# Sheet1.net
KiCad netlist of a schematic drawn in Altium Designer
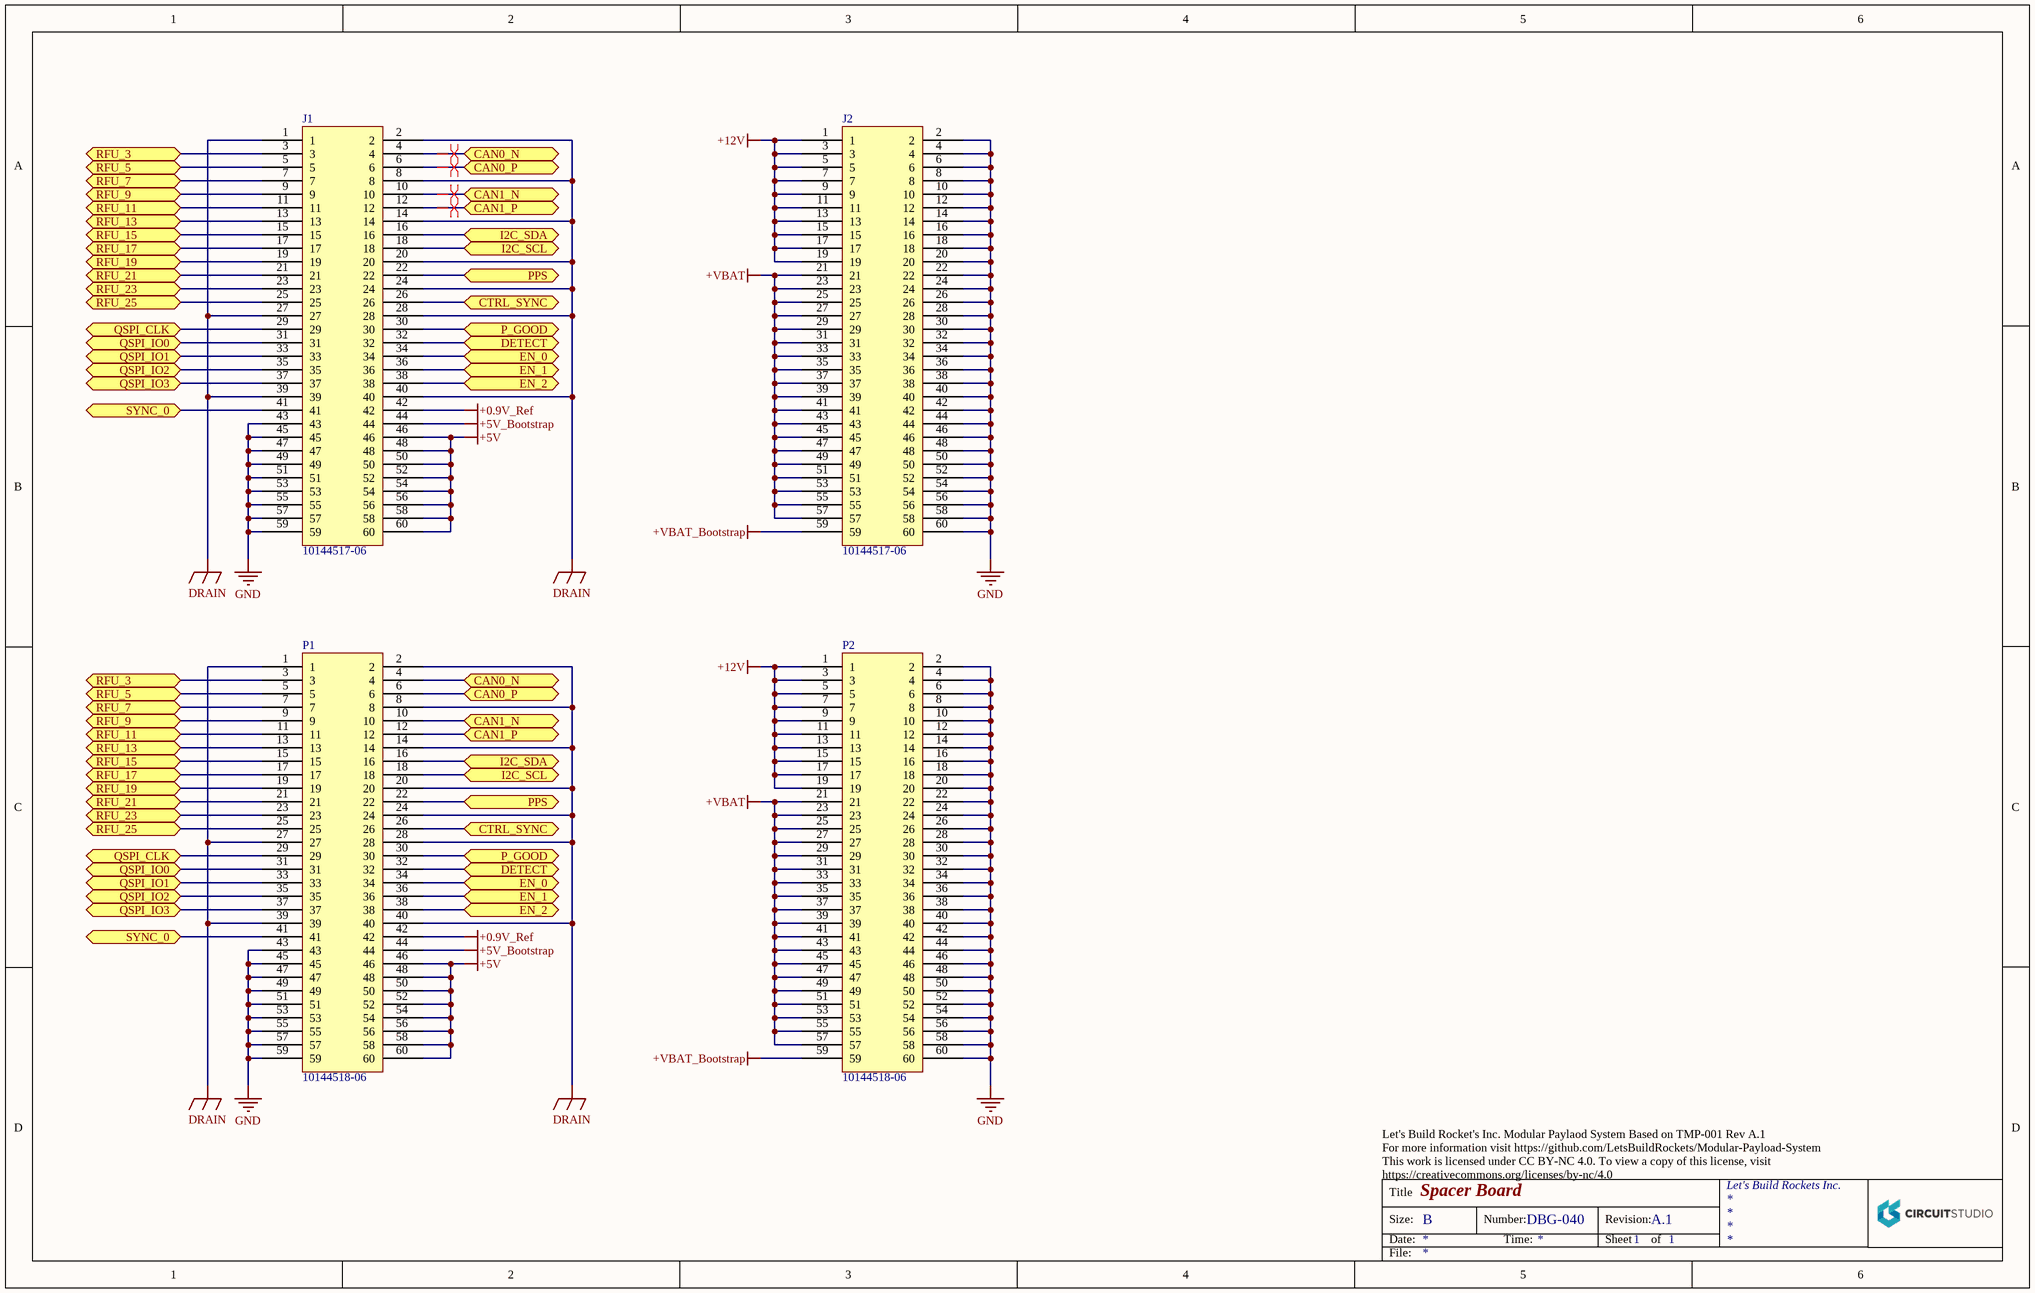
[diagram p0: Sheet1.SchDoc]

(export (version "E")
  (design (tool "Eeschema 10.0.6"))
  (components
    (comp (ref "J1")
      (value "10144517-06")
      (footprint "10144517-062802LF")
      (libsource (lib "ModularPayload") (part "10144517-06"))
    )
    (comp (ref "J2")
      (value "10144517-06")
      (footprint "10144517-062802LF")
      (libsource (lib "ModularPayload") (part "10144517-06"))
    )
    (comp (ref "P1")
      (value "10144518-06")
      (footprint "10144518-064802LF")
      (libsource (lib "ModularPayload") (part "10144518-06"))
    )
    (comp (ref "P2")
      (value "10144518-06")
      (footprint "10144518-064802LF")
      (libsource (lib "ModularPayload") (part "10144518-06"))
    )
  )
  (nets
    (net (code "1") (name "+0.9V_Ref") (class "Default")
      (node (ref "J1") (pin "42") (pinfunction "42_42") (pintype "passive"))
      (node (ref "P1") (pin "42") (pinfunction "42_42") (pintype "passive"))
    )
    (net (code "2") (name "+5V") (class "Default")
      (node (ref "J1") (pin "46") (pinfunction "46_46") (pintype "passive"))
      (node (ref "J1") (pin "48") (pinfunction "48_48") (pintype "passive"))
      (node (ref "J1") (pin "50") (pinfunction "50_50") (pintype "passive"))
      (node (ref "J1") (pin "52") (pinfunction "52_52") (pintype "passive"))
      (node (ref "J1") (pin "54") (pinfunction "54_54") (pintype "passive"))
      (node (ref "J1") (pin "56") (pinfunction "56_56") (pintype "passive"))
      (node (ref "J1") (pin "58") (pinfunction "58_58") (pintype "passive"))
      (node (ref "J1") (pin "60") (pinfunction "60_60") (pintype "passive"))
      (node (ref "P1") (pin "46") (pinfunction "46_46") (pintype "passive"))
      (node (ref "P1") (pin "48") (pinfunction "48_48") (pintype "passive"))
      (node (ref "P1") (pin "50") (pinfunction "50_50") (pintype "passive"))
      (node (ref "P1") (pin "52") (pinfunction "52_52") (pintype "passive"))
      (node (ref "P1") (pin "54") (pinfunction "54_54") (pintype "passive"))
      (node (ref "P1") (pin "56") (pinfunction "56_56") (pintype "passive"))
      (node (ref "P1") (pin "58") (pinfunction "58_58") (pintype "passive"))
      (node (ref "P1") (pin "60") (pinfunction "60_60") (pintype "passive"))
    )
    (net (code "3") (name "+5V_Bootstrap") (class "Default")
      (node (ref "J1") (pin "44") (pinfunction "44_44") (pintype "passive"))
      (node (ref "P1") (pin "44") (pinfunction "44_44") (pintype "passive"))
    )
    (net (code "4") (name "+12V") (class "Default")
      (node (ref "J2") (pin "1") (pinfunction "1_1") (pintype "passive"))
      (node (ref "J2") (pin "11") (pinfunction "11_11") (pintype "passive"))
      (node (ref "J2") (pin "13") (pinfunction "13_13") (pintype "passive"))
      (node (ref "J2") (pin "15") (pinfunction "15_15") (pintype "passive"))
      (node (ref "J2") (pin "17") (pinfunction "17_17") (pintype "passive"))
      (node (ref "J2") (pin "19") (pinfunction "19_19") (pintype "passive"))
      (node (ref "J2") (pin "3") (pinfunction "3_3") (pintype "passive"))
      (node (ref "J2") (pin "5") (pinfunction "5_5") (pintype "passive"))
      (node (ref "J2") (pin "7") (pinfunction "7_7") (pintype "passive"))
      (node (ref "J2") (pin "9") (pinfunction "9_9") (pintype "passive"))
      (node (ref "P2") (pin "1") (pinfunction "1_1") (pintype "passive"))
      (node (ref "P2") (pin "11") (pinfunction "11_11") (pintype "passive"))
      (node (ref "P2") (pin "13") (pinfunction "13_13") (pintype "passive"))
      (node (ref "P2") (pin "15") (pinfunction "15_15") (pintype "passive"))
      (node (ref "P2") (pin "17") (pinfunction "17_17") (pintype "passive"))
      (node (ref "P2") (pin "19") (pinfunction "19_19") (pintype "passive"))
      (node (ref "P2") (pin "3") (pinfunction "3_3") (pintype "passive"))
      (node (ref "P2") (pin "5") (pinfunction "5_5") (pintype "passive"))
      (node (ref "P2") (pin "7") (pinfunction "7_7") (pintype "passive"))
      (node (ref "P2") (pin "9") (pinfunction "9_9") (pintype "passive"))
    )
    (net (code "5") (name "+VBAT") (class "Default")
      (node (ref "J2") (pin "21") (pinfunction "21_21") (pintype "passive"))
      (node (ref "J2") (pin "23") (pinfunction "23_23") (pintype "passive"))
      (node (ref "J2") (pin "25") (pinfunction "25_25") (pintype "passive"))
      (node (ref "J2") (pin "27") (pinfunction "27_27") (pintype "passive"))
      (node (ref "J2") (pin "29") (pinfunction "29_29") (pintype "passive"))
      (node (ref "J2") (pin "31") (pinfunction "31_31") (pintype "passive"))
      (node (ref "J2") (pin "33") (pinfunction "33_33") (pintype "passive"))
      (node (ref "J2") (pin "35") (pinfunction "35_35") (pintype "passive"))
      (node (ref "J2") (pin "37") (pinfunction "37_37") (pintype "passive"))
      (node (ref "J2") (pin "39") (pinfunction "39_39") (pintype "passive"))
      (node (ref "J2") (pin "41") (pinfunction "41_41") (pintype "passive"))
      (node (ref "J2") (pin "43") (pinfunction "43_43") (pintype "passive"))
      (node (ref "J2") (pin "45") (pinfunction "45_45") (pintype "passive"))
      (node (ref "J2") (pin "47") (pinfunction "47_47") (pintype "passive"))
      (node (ref "J2") (pin "49") (pinfunction "49_49") (pintype "passive"))
      (node (ref "J2") (pin "51") (pinfunction "51_51") (pintype "passive"))
      (node (ref "J2") (pin "53") (pinfunction "53_53") (pintype "passive"))
      (node (ref "J2") (pin "55") (pinfunction "55_55") (pintype "passive"))
      (node (ref "J2") (pin "57") (pinfunction "57_57") (pintype "passive"))
      (node (ref "P2") (pin "21") (pinfunction "21_21") (pintype "passive"))
      (node (ref "P2") (pin "23") (pinfunction "23_23") (pintype "passive"))
      (node (ref "P2") (pin "25") (pinfunction "25_25") (pintype "passive"))
      (node (ref "P2") (pin "27") (pinfunction "27_27") (pintype "passive"))
      (node (ref "P2") (pin "29") (pinfunction "29_29") (pintype "passive"))
      (node (ref "P2") (pin "31") (pinfunction "31_31") (pintype "passive"))
      (node (ref "P2") (pin "33") (pinfunction "33_33") (pintype "passive"))
      (node (ref "P2") (pin "35") (pinfunction "35_35") (pintype "passive"))
      (node (ref "P2") (pin "37") (pinfunction "37_37") (pintype "passive"))
      (node (ref "P2") (pin "39") (pinfunction "39_39") (pintype "passive"))
      (node (ref "P2") (pin "41") (pinfunction "41_41") (pintype "passive"))
      (node (ref "P2") (pin "43") (pinfunction "43_43") (pintype "passive"))
      (node (ref "P2") (pin "45") (pinfunction "45_45") (pintype "passive"))
      (node (ref "P2") (pin "47") (pinfunction "47_47") (pintype "passive"))
      (node (ref "P2") (pin "49") (pinfunction "49_49") (pintype "passive"))
      (node (ref "P2") (pin "51") (pinfunction "51_51") (pintype "passive"))
      (node (ref "P2") (pin "53") (pinfunction "53_53") (pintype "passive"))
      (node (ref "P2") (pin "55") (pinfunction "55_55") (pintype "passive"))
      (node (ref "P2") (pin "57") (pinfunction "57_57") (pintype "passive"))
    )
    (net (code "6") (name "+VBAT_Bootstrap") (class "Default")
      (node (ref "J2") (pin "59") (pinfunction "59_59") (pintype "passive"))
      (node (ref "P2") (pin "59") (pinfunction "59_59") (pintype "passive"))
    )
    (net (code "7") (name "/CAN0_N") (class "Default")
      (node (ref "J1") (pin "4") (pinfunction "4_4") (pintype "passive"))
      (node (ref "P1") (pin "4") (pinfunction "4_4") (pintype "passive"))
    )
    (net (code "8") (name "/CAN0_P") (class "Default")
      (node (ref "J1") (pin "6") (pinfunction "6_6") (pintype "passive"))
      (node (ref "P1") (pin "6") (pinfunction "6_6") (pintype "passive"))
    )
    (net (code "9") (name "/CAN1_N") (class "Default")
      (node (ref "J1") (pin "10") (pinfunction "10_10") (pintype "passive"))
      (node (ref "P1") (pin "10") (pinfunction "10_10") (pintype "passive"))
    )
    (net (code "10") (name "/CAN1_P") (class "Default")
      (node (ref "J1") (pin "12") (pinfunction "12_12") (pintype "passive"))
      (node (ref "P1") (pin "12") (pinfunction "12_12") (pintype "passive"))
    )
    (net (code "11") (name "/CTRL_SYNC") (class "Default")
      (node (ref "J1") (pin "26") (pinfunction "26_26") (pintype "passive"))
      (node (ref "P1") (pin "26") (pinfunction "26_26") (pintype "passive"))
    )
    (net (code "12") (name "/DETECT") (class "Default")
      (node (ref "J1") (pin "32") (pinfunction "32_32") (pintype "passive"))
      (node (ref "P1") (pin "32") (pinfunction "32_32") (pintype "passive"))
    )
    (net (code "13") (name "/EN_0") (class "Default")
      (node (ref "J1") (pin "34") (pinfunction "34_34") (pintype "passive"))
      (node (ref "P1") (pin "34") (pinfunction "34_34") (pintype "passive"))
    )
    (net (code "14") (name "/EN_1") (class "Default")
      (node (ref "J1") (pin "36") (pinfunction "36_36") (pintype "passive"))
      (node (ref "P1") (pin "36") (pinfunction "36_36") (pintype "passive"))
    )
    (net (code "15") (name "/EN_2") (class "Default")
      (node (ref "J1") (pin "38") (pinfunction "38_38") (pintype "passive"))
      (node (ref "P1") (pin "38") (pinfunction "38_38") (pintype "passive"))
    )
    (net (code "16") (name "/I2C_SCL") (class "Default")
      (node (ref "J1") (pin "18") (pinfunction "18_18") (pintype "passive"))
      (node (ref "P1") (pin "18") (pinfunction "18_18") (pintype "passive"))
    )
    (net (code "17") (name "/I2C_SDA") (class "Default")
      (node (ref "J1") (pin "16") (pinfunction "16_16") (pintype "passive"))
      (node (ref "P1") (pin "16") (pinfunction "16_16") (pintype "passive"))
    )
    (net (code "18") (name "/PPS") (class "Default")
      (node (ref "J1") (pin "22") (pinfunction "22_22") (pintype "passive"))
      (node (ref "P1") (pin "22") (pinfunction "22_22") (pintype "passive"))
    )
    (net (code "19") (name "/P_GOOD") (class "Default")
      (node (ref "J1") (pin "30") (pinfunction "30_30") (pintype "passive"))
      (node (ref "P1") (pin "30") (pinfunction "30_30") (pintype "passive"))
    )
    (net (code "20") (name "/QSPI_CLK") (class "Default")
      (node (ref "J1") (pin "29") (pinfunction "29_29") (pintype "passive"))
      (node (ref "P1") (pin "29") (pinfunction "29_29") (pintype "passive"))
    )
    (net (code "21") (name "/QSPI_IO0") (class "Default")
      (node (ref "J1") (pin "31") (pinfunction "31_31") (pintype "passive"))
      (node (ref "P1") (pin "31") (pinfunction "31_31") (pintype "passive"))
    )
    (net (code "22") (name "/QSPI_IO1") (class "Default")
      (node (ref "J1") (pin "33") (pinfunction "33_33") (pintype "passive"))
      (node (ref "P1") (pin "33") (pinfunction "33_33") (pintype "passive"))
    )
    (net (code "23") (name "/QSPI_IO2") (class "Default")
      (node (ref "J1") (pin "35") (pinfunction "35_35") (pintype "passive"))
      (node (ref "P1") (pin "35") (pinfunction "35_35") (pintype "passive"))
    )
    (net (code "24") (name "/QSPI_IO3") (class "Default")
      (node (ref "J1") (pin "37") (pinfunction "37_37") (pintype "passive"))
      (node (ref "P1") (pin "37") (pinfunction "37_37") (pintype "passive"))
    )
    (net (code "25") (name "/RFU_3") (class "Default")
      (node (ref "J1") (pin "3") (pinfunction "3_3") (pintype "passive"))
      (node (ref "P1") (pin "3") (pinfunction "3_3") (pintype "passive"))
    )
    (net (code "26") (name "/RFU_5") (class "Default")
      (node (ref "J1") (pin "5") (pinfunction "5_5") (pintype "passive"))
      (node (ref "P1") (pin "5") (pinfunction "5_5") (pintype "passive"))
    )
    (net (code "27") (name "/RFU_7") (class "Default")
      (node (ref "J1") (pin "7") (pinfunction "7_7") (pintype "passive"))
      (node (ref "P1") (pin "7") (pinfunction "7_7") (pintype "passive"))
    )
    (net (code "28") (name "/RFU_9") (class "Default")
      (node (ref "J1") (pin "9") (pinfunction "9_9") (pintype "passive"))
      (node (ref "P1") (pin "9") (pinfunction "9_9") (pintype "passive"))
    )
    (net (code "29") (name "/RFU_11") (class "Default")
      (node (ref "J1") (pin "11") (pinfunction "11_11") (pintype "passive"))
      (node (ref "P1") (pin "11") (pinfunction "11_11") (pintype "passive"))
    )
    (net (code "30") (name "/RFU_13") (class "Default")
      (node (ref "J1") (pin "13") (pinfunction "13_13") (pintype "passive"))
      (node (ref "P1") (pin "13") (pinfunction "13_13") (pintype "passive"))
    )
    (net (code "31") (name "/RFU_15") (class "Default")
      (node (ref "J1") (pin "15") (pinfunction "15_15") (pintype "passive"))
      (node (ref "P1") (pin "15") (pinfunction "15_15") (pintype "passive"))
    )
    (net (code "32") (name "/RFU_17") (class "Default")
      (node (ref "J1") (pin "17") (pinfunction "17_17") (pintype "passive"))
      (node (ref "P1") (pin "17") (pinfunction "17_17") (pintype "passive"))
    )
    (net (code "33") (name "/RFU_19") (class "Default")
      (node (ref "J1") (pin "19") (pinfunction "19_19") (pintype "passive"))
      (node (ref "P1") (pin "19") (pinfunction "19_19") (pintype "passive"))
    )
    (net (code "34") (name "/RFU_21") (class "Default")
      (node (ref "J1") (pin "21") (pinfunction "21_21") (pintype "passive"))
      (node (ref "P1") (pin "21") (pinfunction "21_21") (pintype "passive"))
    )
    (net (code "35") (name "/RFU_23") (class "Default")
      (node (ref "J1") (pin "23") (pinfunction "23_23") (pintype "passive"))
      (node (ref "P1") (pin "23") (pinfunction "23_23") (pintype "passive"))
    )
    (net (code "36") (name "/RFU_25") (class "Default")
      (node (ref "J1") (pin "25") (pinfunction "25_25") (pintype "passive"))
      (node (ref "P1") (pin "25") (pinfunction "25_25") (pintype "passive"))
    )
    (net (code "37") (name "/SYNC_0") (class "Default")
      (node (ref "J1") (pin "41") (pinfunction "41_41") (pintype "passive"))
      (node (ref "P1") (pin "41") (pinfunction "41_41") (pintype "passive"))
    )
    (net (code "38") (name "DRAIN") (class "Default")
      (node (ref "J1") (pin "1") (pinfunction "1_1") (pintype "passive"))
      (node (ref "J1") (pin "14") (pinfunction "14_14") (pintype "passive"))
      (node (ref "J1") (pin "2") (pinfunction "2_2") (pintype "passive"))
      (node (ref "J1") (pin "20") (pinfunction "20_20") (pintype "passive"))
      (node (ref "J1") (pin "24") (pinfunction "24_24") (pintype "passive"))
      (node (ref "J1") (pin "27") (pinfunction "27_27") (pintype "passive"))
      (node (ref "J1") (pin "28") (pinfunction "28_28") (pintype "passive"))
      (node (ref "J1") (pin "39") (pinfunction "39_39") (pintype "passive"))
      (node (ref "J1") (pin "40") (pinfunction "40_40") (pintype "passive"))
      (node (ref "J1") (pin "8") (pinfunction "8_8") (pintype "passive"))
      (node (ref "P1") (pin "1") (pinfunction "1_1") (pintype "passive"))
      (node (ref "P1") (pin "14") (pinfunction "14_14") (pintype "passive"))
      (node (ref "P1") (pin "2") (pinfunction "2_2") (pintype "passive"))
      (node (ref "P1") (pin "20") (pinfunction "20_20") (pintype "passive"))
      (node (ref "P1") (pin "24") (pinfunction "24_24") (pintype "passive"))
      (node (ref "P1") (pin "27") (pinfunction "27_27") (pintype "passive"))
      (node (ref "P1") (pin "28") (pinfunction "28_28") (pintype "passive"))
      (node (ref "P1") (pin "39") (pinfunction "39_39") (pintype "passive"))
      (node (ref "P1") (pin "40") (pinfunction "40_40") (pintype "passive"))
      (node (ref "P1") (pin "8") (pinfunction "8_8") (pintype "passive"))
    )
    (net (code "39") (name "GND") (class "Default")
      (node (ref "J1") (pin "43") (pinfunction "43_43") (pintype "passive"))
      (node (ref "J1") (pin "45") (pinfunction "45_45") (pintype "passive"))
      (node (ref "J1") (pin "47") (pinfunction "47_47") (pintype "passive"))
      (node (ref "J1") (pin "49") (pinfunction "49_49") (pintype "passive"))
      (node (ref "J1") (pin "51") (pinfunction "51_51") (pintype "passive"))
      (node (ref "J1") (pin "53") (pinfunction "53_53") (pintype "passive"))
      (node (ref "J1") (pin "55") (pinfunction "55_55") (pintype "passive"))
      (node (ref "J1") (pin "57") (pinfunction "57_57") (pintype "passive"))
      (node (ref "J1") (pin "59") (pinfunction "59_59") (pintype "passive"))
      (node (ref "J2") (pin "10") (pinfunction "10_10") (pintype "passive"))
      (node (ref "J2") (pin "12") (pinfunction "12_12") (pintype "passive"))
      (node (ref "J2") (pin "14") (pinfunction "14_14") (pintype "passive"))
      (node (ref "J2") (pin "16") (pinfunction "16_16") (pintype "passive"))
      (node (ref "J2") (pin "18") (pinfunction "18_18") (pintype "passive"))
      (node (ref "J2") (pin "2") (pinfunction "2_2") (pintype "passive"))
      (node (ref "J2") (pin "20") (pinfunction "20_20") (pintype "passive"))
      (node (ref "J2") (pin "22") (pinfunction "22_22") (pintype "passive"))
      (node (ref "J2") (pin "24") (pinfunction "24_24") (pintype "passive"))
      (node (ref "J2") (pin "26") (pinfunction "26_26") (pintype "passive"))
      (node (ref "J2") (pin "28") (pinfunction "28_28") (pintype "passive"))
      (node (ref "J2") (pin "30") (pinfunction "30_30") (pintype "passive"))
      (node (ref "J2") (pin "32") (pinfunction "32_32") (pintype "passive"))
      (node (ref "J2") (pin "34") (pinfunction "34_34") (pintype "passive"))
      (node (ref "J2") (pin "36") (pinfunction "36_36") (pintype "passive"))
      (node (ref "J2") (pin "38") (pinfunction "38_38") (pintype "passive"))
      (node (ref "J2") (pin "4") (pinfunction "4_4") (pintype "passive"))
      (node (ref "J2") (pin "40") (pinfunction "40_40") (pintype "passive"))
      (node (ref "J2") (pin "42") (pinfunction "42_42") (pintype "passive"))
      (node (ref "J2") (pin "44") (pinfunction "44_44") (pintype "passive"))
      (node (ref "J2") (pin "46") (pinfunction "46_46") (pintype "passive"))
      (node (ref "J2") (pin "48") (pinfunction "48_48") (pintype "passive"))
      (node (ref "J2") (pin "50") (pinfunction "50_50") (pintype "passive"))
      (node (ref "J2") (pin "52") (pinfunction "52_52") (pintype "passive"))
      (node (ref "J2") (pin "54") (pinfunction "54_54") (pintype "passive"))
      (node (ref "J2") (pin "56") (pinfunction "56_56") (pintype "passive"))
      (node (ref "J2") (pin "58") (pinfunction "58_58") (pintype "passive"))
      (node (ref "J2") (pin "6") (pinfunction "6_6") (pintype "passive"))
      (node (ref "J2") (pin "60") (pinfunction "60_60") (pintype "passive"))
      (node (ref "J2") (pin "8") (pinfunction "8_8") (pintype "passive"))
      (node (ref "P1") (pin "43") (pinfunction "43_43") (pintype "passive"))
      (node (ref "P1") (pin "45") (pinfunction "45_45") (pintype "passive"))
      (node (ref "P1") (pin "47") (pinfunction "47_47") (pintype "passive"))
      (node (ref "P1") (pin "49") (pinfunction "49_49") (pintype "passive"))
      (node (ref "P1") (pin "51") (pinfunction "51_51") (pintype "passive"))
      (node (ref "P1") (pin "53") (pinfunction "53_53") (pintype "passive"))
      (node (ref "P1") (pin "55") (pinfunction "55_55") (pintype "passive"))
      (node (ref "P1") (pin "57") (pinfunction "57_57") (pintype "passive"))
      (node (ref "P1") (pin "59") (pinfunction "59_59") (pintype "passive"))
      (node (ref "P2") (pin "10") (pinfunction "10_10") (pintype "passive"))
      (node (ref "P2") (pin "12") (pinfunction "12_12") (pintype "passive"))
      (node (ref "P2") (pin "14") (pinfunction "14_14") (pintype "passive"))
      (node (ref "P2") (pin "16") (pinfunction "16_16") (pintype "passive"))
      (node (ref "P2") (pin "18") (pinfunction "18_18") (pintype "passive"))
      (node (ref "P2") (pin "2") (pinfunction "2_2") (pintype "passive"))
      (node (ref "P2") (pin "20") (pinfunction "20_20") (pintype "passive"))
      (node (ref "P2") (pin "22") (pinfunction "22_22") (pintype "passive"))
      (node (ref "P2") (pin "24") (pinfunction "24_24") (pintype "passive"))
      (node (ref "P2") (pin "26") (pinfunction "26_26") (pintype "passive"))
      (node (ref "P2") (pin "28") (pinfunction "28_28") (pintype "passive"))
      (node (ref "P2") (pin "30") (pinfunction "30_30") (pintype "passive"))
      (node (ref "P2") (pin "32") (pinfunction "32_32") (pintype "passive"))
      (node (ref "P2") (pin "34") (pinfunction "34_34") (pintype "passive"))
      (node (ref "P2") (pin "36") (pinfunction "36_36") (pintype "passive"))
      (node (ref "P2") (pin "38") (pinfunction "38_38") (pintype "passive"))
      (node (ref "P2") (pin "4") (pinfunction "4_4") (pintype "passive"))
      (node (ref "P2") (pin "40") (pinfunction "40_40") (pintype "passive"))
      (node (ref "P2") (pin "42") (pinfunction "42_42") (pintype "passive"))
      (node (ref "P2") (pin "44") (pinfunction "44_44") (pintype "passive"))
      (node (ref "P2") (pin "46") (pinfunction "46_46") (pintype "passive"))
      (node (ref "P2") (pin "48") (pinfunction "48_48") (pintype "passive"))
      (node (ref "P2") (pin "50") (pinfunction "50_50") (pintype "passive"))
      (node (ref "P2") (pin "52") (pinfunction "52_52") (pintype "passive"))
      (node (ref "P2") (pin "54") (pinfunction "54_54") (pintype "passive"))
      (node (ref "P2") (pin "56") (pinfunction "56_56") (pintype "passive"))
      (node (ref "P2") (pin "58") (pinfunction "58_58") (pintype "passive"))
      (node (ref "P2") (pin "6") (pinfunction "6_6") (pintype "passive"))
      (node (ref "P2") (pin "60") (pinfunction "60_60") (pintype "passive"))
      (node (ref "P2") (pin "8") (pinfunction "8_8") (pintype "passive"))
    )
  )
)
